# module_ESP07.net
KiCad netlist of a schematic drawn in EAGLE
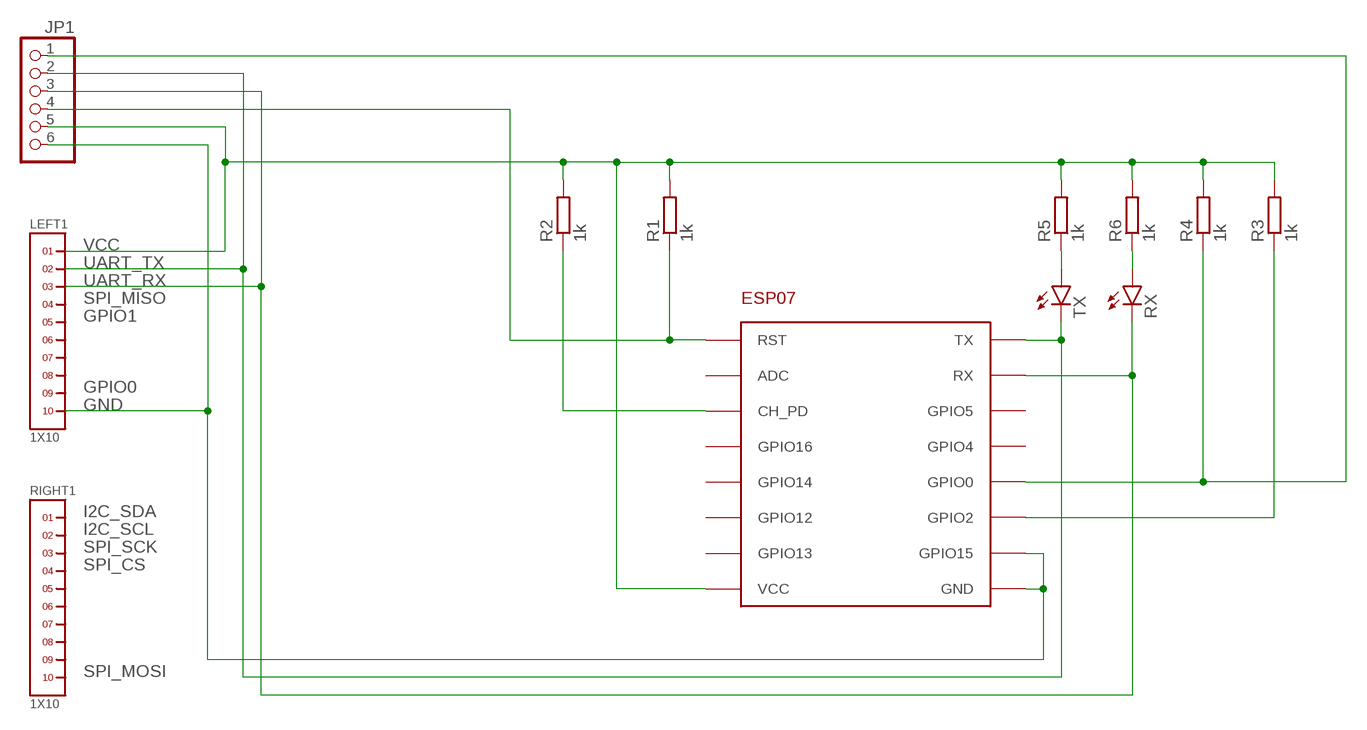
[diagram p0: schematic, sheet 1]

(export (version "E")
  (design (tool "Eeschema 10.0.6"))
  (components
    (comp (ref "JP1")
      (value "PINHD-1X6")
      (footprint "eagle-import:1X06")
      (libsource (lib "eagle-import") (part "PINHD-1X6"))
    )
    (comp (ref "LEFT1")
      (value "1X10")
      (footprint "eagle-import:1X10")
      (libsource (lib "eagle-import") (part "1X10"))
    )
    (comp (ref "R1")
      (value "1k")
      (footprint "eagle-import:R0603")
      (libsource (lib "eagle-import") (part "R-EU_R0603"))
    )
    (comp (ref "R2")
      (value "1k")
      (footprint "eagle-import:R0603")
      (libsource (lib "eagle-import") (part "R-EU_R0603"))
    )
    (comp (ref "R3")
      (value "1k")
      (footprint "eagle-import:R0603")
      (libsource (lib "eagle-import") (part "R-EU_R0603"))
    )
    (comp (ref "R4")
      (value "1k")
      (footprint "eagle-import:R0603")
      (libsource (lib "eagle-import") (part "R-EU_R0603"))
    )
    (comp (ref "R5")
      (value "1k")
      (footprint "eagle-import:R0603")
      (libsource (lib "eagle-import") (part "R-EU_R0603"))
    )
    (comp (ref "R6")
      (value "1k")
      (footprint "eagle-import:R0603")
      (libsource (lib "eagle-import") (part "R-EU_R0603"))
    )
    (comp (ref "RIGHT1")
      (value "1X10")
      (footprint "eagle-import:1X10")
      (libsource (lib "eagle-import") (part "1X10"))
    )
    (comp (ref "RX")
      (value "LEDCHIPLED_0603")
      (footprint "eagle-import:CHIPLED_0603")
      (libsource (lib "eagle-import") (part "LEDCHIPLED_0603"))
    )
    (comp (ref "TX")
      (value "LEDCHIPLED_0603")
      (footprint "eagle-import:CHIPLED_0603")
      (libsource (lib "eagle-import") (part "LEDCHIPLED_0603"))
    )
    (comp (ref "U$1")
      (value "ESP-07")
      (footprint "eagle-import:ESP07")
      (libsource (lib "eagle-import") (part "ESP-07"))
    )
  )
  (nets
    (net (code "1") (name "Net-(JP1-Pad1)") (class "Default")
      (node (ref "JP1") (pin "1") (pinfunction "1_1") (pintype "passive"))
      (node (ref "R4") (pin "1") (pinfunction "1_1") (pintype "passive"))
      (node (ref "U$1") (pin "GPIO0") (pinfunction "GPIO0_GPIO0") (pintype "bidirectional"))
    )
    (net (code "2") (name "Net-(JP1-Pad2)") (class "Default")
      (node (ref "JP1") (pin "2") (pinfunction "2_2") (pintype "passive"))
      (node (ref "LEFT1") (pin "2") (pinfunction "2_2") (pintype "bidirectional"))
      (node (ref "TX") (pin "C") (pinfunction "C_C") (pintype "passive"))
      (node (ref "U$1") (pin "TX") (pinfunction "TX_TX") (pintype "bidirectional"))
    )
    (net (code "3") (name "Net-(JP1-Pad3)") (class "Default")
      (node (ref "JP1") (pin "3") (pinfunction "3_3") (pintype "passive"))
      (node (ref "LEFT1") (pin "3") (pinfunction "3_3") (pintype "bidirectional"))
      (node (ref "RX") (pin "C") (pinfunction "C_C") (pintype "passive"))
      (node (ref "U$1") (pin "RX") (pinfunction "RX_RX") (pintype "bidirectional"))
    )
    (net (code "4") (name "Net-(JP1-Pad4)") (class "Default")
      (node (ref "JP1") (pin "4") (pinfunction "4_4") (pintype "passive"))
      (node (ref "R1") (pin "1") (pinfunction "1_1") (pintype "passive"))
      (node (ref "U$1") (pin "RST") (pinfunction "RST_RST") (pintype "bidirectional"))
    )
    (net (code "5") (name "Net-(JP1-Pad5)") (class "Default")
      (node (ref "JP1") (pin "5") (pinfunction "5_5") (pintype "passive"))
      (node (ref "LEFT1") (pin "1") (pinfunction "1_1") (pintype "bidirectional"))
      (node (ref "R1") (pin "2") (pinfunction "2_2") (pintype "passive"))
      (node (ref "R2") (pin "2") (pinfunction "2_2") (pintype "passive"))
      (node (ref "R3") (pin "2") (pinfunction "2_2") (pintype "passive"))
      (node (ref "R4") (pin "2") (pinfunction "2_2") (pintype "passive"))
      (node (ref "R5") (pin "2") (pinfunction "2_2") (pintype "passive"))
      (node (ref "R6") (pin "2") (pinfunction "2_2") (pintype "passive"))
      (node (ref "U$1") (pin "VCC") (pinfunction "VCC_VCC") (pintype "bidirectional"))
    )
    (net (code "6") (name "Net-(JP1-Pad6)") (class "Default")
      (node (ref "JP1") (pin "6") (pinfunction "6_6") (pintype "passive"))
      (node (ref "LEFT1") (pin "10") (pinfunction "10_10") (pintype "bidirectional"))
      (node (ref "U$1") (pin "GND") (pinfunction "GND_GND") (pintype "bidirectional"))
      (node (ref "U$1") (pin "GPIO15") (pinfunction "GPIO15_GPIO15") (pintype "bidirectional"))
    )
    (net (code "7") (name "Net-(R2-Pad1)") (class "Default")
      (node (ref "R2") (pin "1") (pinfunction "1_1") (pintype "passive"))
      (node (ref "U$1") (pin "CH_PD") (pinfunction "CH_PD_CH_PD") (pintype "bidirectional"))
    )
    (net (code "8") (name "Net-(R3-Pad1)") (class "Default")
      (node (ref "R3") (pin "1") (pinfunction "1_1") (pintype "passive"))
      (node (ref "U$1") (pin "GPIO2") (pinfunction "GPIO2_GPIO2") (pintype "bidirectional"))
    )
    (net (code "9") (name "Net-(R5-Pad1)") (class "Default")
      (node (ref "R5") (pin "1") (pinfunction "1_1") (pintype "passive"))
      (node (ref "TX") (pin "A") (pinfunction "A_A") (pintype "passive"))
    )
    (net (code "10") (name "Net-(R6-Pad1)") (class "Default")
      (node (ref "R6") (pin "1") (pinfunction "1_1") (pintype "passive"))
      (node (ref "RX") (pin "A") (pinfunction "A_A") (pintype "passive"))
    )
    (net (code "11") (name "unconnected-(LEFT1-Pad4)") (class "Default")
      (node (ref "LEFT1") (pin "4") (pinfunction "4_4") (pintype "bidirectional"))
    )
    (net (code "12") (name "unconnected-(LEFT1-Pad5)") (class "Default")
      (node (ref "LEFT1") (pin "5") (pinfunction "5_5") (pintype "bidirectional"))
    )
    (net (code "13") (name "unconnected-(LEFT1-Pad6)") (class "Default")
      (node (ref "LEFT1") (pin "6") (pinfunction "6_6") (pintype "bidirectional"))
    )
    (net (code "14") (name "unconnected-(LEFT1-Pad7)") (class "Default")
      (node (ref "LEFT1") (pin "7") (pinfunction "7_7") (pintype "bidirectional"))
    )
    (net (code "15") (name "unconnected-(LEFT1-Pad8)") (class "Default")
      (node (ref "LEFT1") (pin "8") (pinfunction "8_8") (pintype "bidirectional"))
    )
    (net (code "16") (name "unconnected-(LEFT1-Pad9)") (class "Default")
      (node (ref "LEFT1") (pin "9") (pinfunction "9_9") (pintype "bidirectional"))
    )
    (net (code "17") (name "unconnected-(RIGHT1-Pad1)") (class "Default")
      (node (ref "RIGHT1") (pin "1") (pinfunction "1_1") (pintype "bidirectional"))
    )
    (net (code "18") (name "unconnected-(RIGHT1-Pad2)") (class "Default")
      (node (ref "RIGHT1") (pin "2") (pinfunction "2_2") (pintype "bidirectional"))
    )
    (net (code "19") (name "unconnected-(RIGHT1-Pad3)") (class "Default")
      (node (ref "RIGHT1") (pin "3") (pinfunction "3_3") (pintype "bidirectional"))
    )
    (net (code "20") (name "unconnected-(RIGHT1-Pad4)") (class "Default")
      (node (ref "RIGHT1") (pin "4") (pinfunction "4_4") (pintype "bidirectional"))
    )
    (net (code "21") (name "unconnected-(RIGHT1-Pad5)") (class "Default")
      (node (ref "RIGHT1") (pin "5") (pinfunction "5_5") (pintype "bidirectional"))
    )
    (net (code "22") (name "unconnected-(RIGHT1-Pad6)") (class "Default")
      (node (ref "RIGHT1") (pin "6") (pinfunction "6_6") (pintype "bidirectional"))
    )
    (net (code "23") (name "unconnected-(RIGHT1-Pad7)") (class "Default")
      (node (ref "RIGHT1") (pin "7") (pinfunction "7_7") (pintype "bidirectional"))
    )
    (net (code "24") (name "unconnected-(RIGHT1-Pad8)") (class "Default")
      (node (ref "RIGHT1") (pin "8") (pinfunction "8_8") (pintype "bidirectional"))
    )
    (net (code "25") (name "unconnected-(RIGHT1-Pad9)") (class "Default")
      (node (ref "RIGHT1") (pin "9") (pinfunction "9_9") (pintype "bidirectional"))
    )
    (net (code "26") (name "unconnected-(RIGHT1-Pad10)") (class "Default")
      (node (ref "RIGHT1") (pin "10") (pinfunction "10_10") (pintype "bidirectional"))
    )
    (net (code "27") (name "unconnected-(U$1-PadADC)") (class "Default")
      (node (ref "U$1") (pin "ADC") (pinfunction "ADC_ADC") (pintype "bidirectional"))
    )
    (net (code "28") (name "unconnected-(U$1-PadGPIO4)") (class "Default")
      (node (ref "U$1") (pin "GPIO4") (pinfunction "GPIO4_GPIO4") (pintype "bidirectional"))
    )
    (net (code "29") (name "unconnected-(U$1-PadGPIO5)") (class "Default")
      (node (ref "U$1") (pin "GPIO5") (pinfunction "GPIO5_GPIO5") (pintype "bidirectional"))
    )
    (net (code "30") (name "unconnected-(U$1-PadGPIO12)") (class "Default")
      (node (ref "U$1") (pin "GPIO12") (pinfunction "GPIO12_GPIO12") (pintype "bidirectional"))
    )
    (net (code "31") (name "unconnected-(U$1-PadGPIO13)") (class "Default")
      (node (ref "U$1") (pin "GPIO13") (pinfunction "GPIO13_GPIO13") (pintype "bidirectional"))
    )
    (net (code "32") (name "unconnected-(U$1-PadGPIO14)") (class "Default")
      (node (ref "U$1") (pin "GPIO14") (pinfunction "GPIO14_GPIO14") (pintype "bidirectional"))
    )
    (net (code "33") (name "unconnected-(U$1-PadGPIO16)") (class "Default")
      (node (ref "U$1") (pin "GPIO16") (pinfunction "GPIO16_GPIO16") (pintype "bidirectional"))
    )
  )
)
